# SMD_DC_DC_Converter_Test_LXDC2HL33A_055.net
KiCad netlist of a schematic drawn in EAGLE
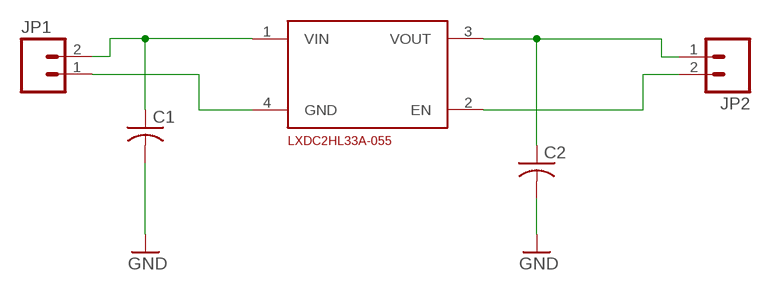
[diagram p0: schematic, sheet 1]

(export (version "E")
  (design (tool "Eeschema 10.0.6"))
  (components
    (comp (ref "C1")
      (value "C-USC0805K")
      (footprint "eagle-import:C0805K")
      (libsource (lib "eagle-import") (part "C-USC0805K"))
    )
    (comp (ref "C2")
      (value "C-USC0805K")
      (footprint "eagle-import:C0805K")
      (libsource (lib "eagle-import") (part "C-USC0805K"))
    )
    (comp (ref "JP1")
      (value "M02LOCK")
      (footprint "eagle-import:1X02_LOCK")
      (libsource (lib "eagle-import") (part "M02LOCK"))
    )
    (comp (ref "JP2")
      (value "M02LOCK")
      (footprint "eagle-import:1X02_LOCK")
      (libsource (lib "eagle-import") (part "M02LOCK"))
    )
    (comp (ref "U$1")
      (value "LXDC2HL33A-055")
      (footprint "eagle-import:LXDC2HL33A-055")
      (libsource (lib "eagle-import") (part "LXDC2HL33A-055"))
    )
  )
  (nets
    (net (code "1") (name "GND") (class "Default")
      (node (ref "C1") (pin "2") (pinfunction "2_2") (pintype "passive"))
      (node (ref "C2") (pin "2") (pinfunction "2_2") (pintype "passive"))
      (node (ref "JP1") (pin "1") (pinfunction "1_1") (pintype "passive"))
      (node (ref "U$1") (pin "4") (pinfunction "GND_4") (pintype "bidirectional"))
    )
    (net (code "2") (name "Net-(U$1-EN)") (class "Default")
      (node (ref "JP2") (pin "2") (pinfunction "2_2") (pintype "passive"))
      (node (ref "U$1") (pin "2") (pinfunction "EN_2") (pintype "bidirectional"))
    )
    (net (code "3") (name "Net-(U$1-VIN)") (class "Default")
      (node (ref "C1") (pin "1") (pinfunction "1_1") (pintype "passive"))
      (node (ref "JP1") (pin "2") (pinfunction "2_2") (pintype "passive"))
      (node (ref "U$1") (pin "1") (pinfunction "VIN_1") (pintype "bidirectional"))
    )
    (net (code "4") (name "Net-(U$1-VOUT)") (class "Default")
      (node (ref "C2") (pin "1") (pinfunction "1_1") (pintype "passive"))
      (node (ref "JP2") (pin "1") (pinfunction "1_1") (pintype "passive"))
      (node (ref "U$1") (pin "3") (pinfunction "VOUT_3") (pintype "bidirectional"))
    )
  )
)
